# LED.net
KiCad netlist of a schematic drawn in EAGLE
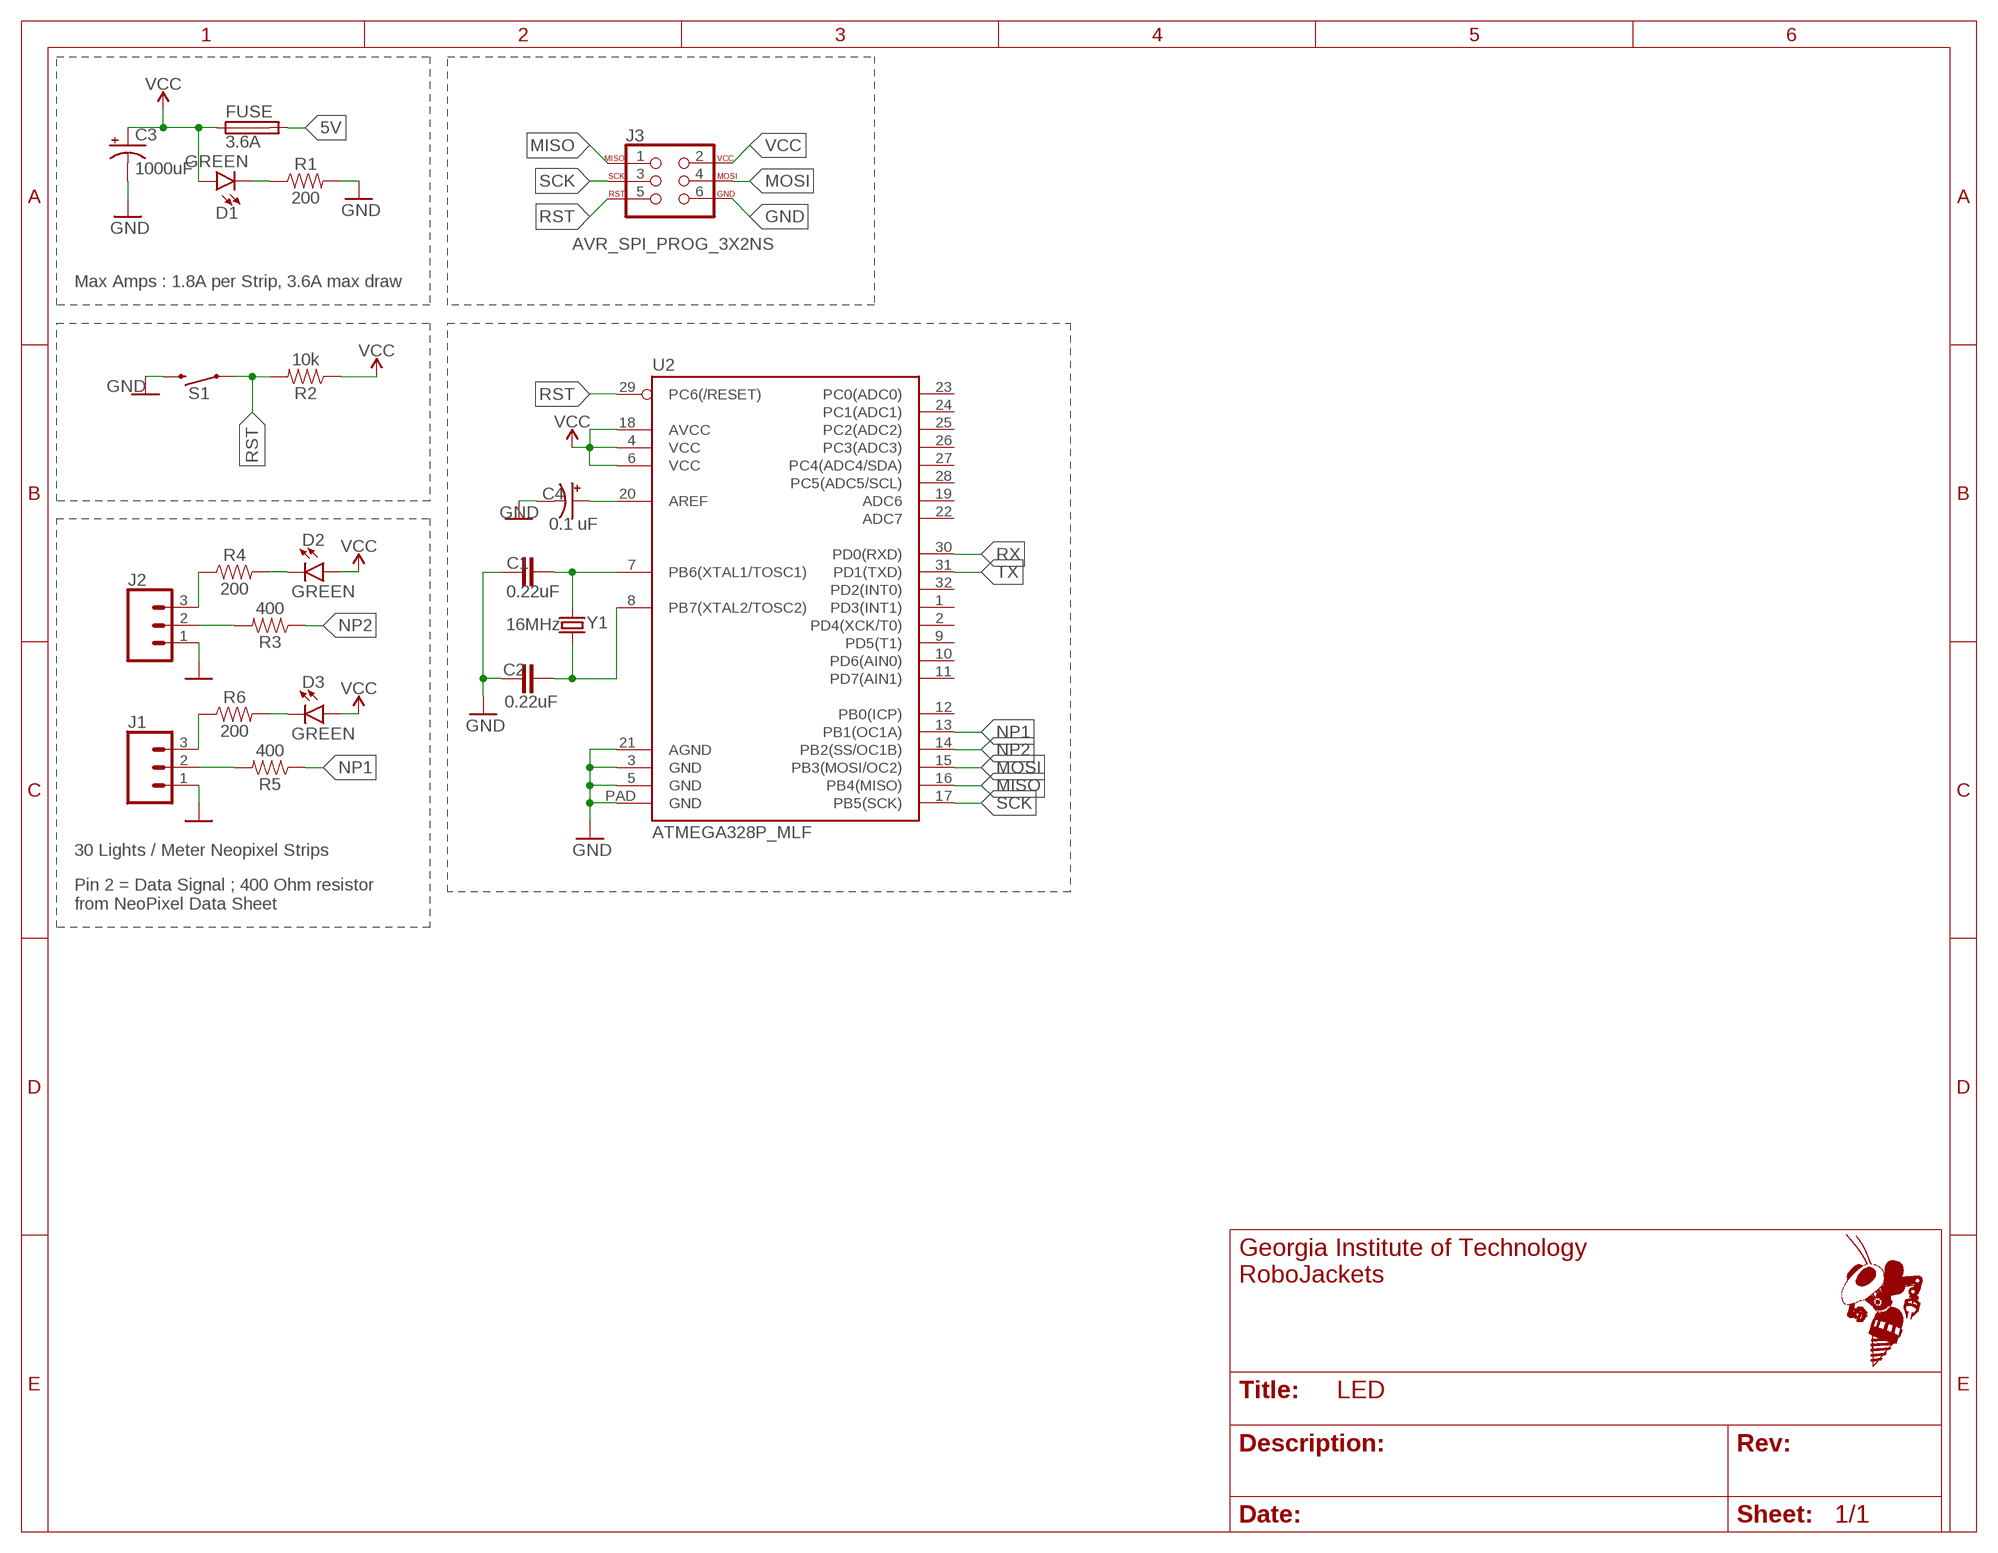
[diagram p0: schematic, sheet 1]

(export (version "E")
  (design (tool "Eeschema 10.0.6"))
  (components
    (comp (ref "C1")
      (value "0.22uF")
      (footprint "eagle-import:0603")
      (libsource (lib "eagle-import") (part "0.22UF-0603-25V-10%"))
    )
    (comp (ref "C2")
      (value "0.22uF")
      (footprint "eagle-import:0603")
      (libsource (lib "eagle-import") (part "0.22UF-0603-25V-10%"))
    )
    (comp (ref "C3")
      (value "1000uF")
      (footprint "eagle-import:CPOL-RADIAL-5MM-10MM")
      (libsource (lib "eagle-import") (part "1000UF-RADIAL-5MM-25V-20%"))
    )
    (comp (ref "C4")
      (value "0.1 uF")
      (footprint "eagle-import:CPOL-RADIAL-5MM-10MM")
      (libsource (lib "eagle-import") (part "1000UF-RADIAL-5MM-25V-20%"))
    )
    (comp (ref "D1")
      (value "GREEN")
      (footprint "eagle-import:LED-0603")
      (libsource (lib "eagle-import") (part "LED-GREEN0603"))
    )
    (comp (ref "D2")
      (value "GREEN")
      (footprint "eagle-import:LED-0603")
      (libsource (lib "eagle-import") (part "LED-GREEN0603"))
    )
    (comp (ref "D3")
      (value "GREEN")
      (footprint "eagle-import:LED-0603")
      (libsource (lib "eagle-import") (part "LED-GREEN0603"))
    )
    (comp (ref "FUSE")
      (value "3.6A")
      (footprint "eagle-import:FUSE_HOLDER")
      (libsource (lib "eagle-import") (part "FUSE_HOLDER"))
    )
    (comp (ref "J1")
      (value "CONN_03")
      (footprint "eagle-import:1X03")
      (fields (field (name "SPICEPREFIX") "J"))
      (libsource (lib "eagle-import") (part "CONN_03"))
    )
    (comp (ref "J2")
      (value "CONN_03")
      (footprint "eagle-import:1X03")
      (fields (field (name "SPICEPREFIX") "J"))
      (libsource (lib "eagle-import") (part "CONN_03"))
    )
    (comp (ref "J3")
      (value "AVR_SPI_PROG_3X2NS")
      (footprint "eagle-import:2X3-NS")
      (libsource (lib "eagle-import") (part "AVR_SPI_PROG_3X2NS"))
    )
    (comp (ref "R1")
      (value "200")
      (footprint "eagle-import:0603")
      (libsource (lib "eagle-import") (part "470OHM-0603-1/10W-1%"))
    )
    (comp (ref "R2")
      (value "10k")
      (footprint "eagle-import:0603")
      (libsource (lib "eagle-import") (part "470OHM-0603-1/10W-1%"))
    )
    (comp (ref "R3")
      (value "400")
      (footprint "eagle-import:0603")
      (libsource (lib "eagle-import") (part "470OHM-0603-1/10W-1%"))
    )
    (comp (ref "R4")
      (value "200")
      (footprint "eagle-import:0603")
      (libsource (lib "eagle-import") (part "470OHM-0603-1/10W-1%"))
    )
    (comp (ref "R5")
      (value "400")
      (footprint "eagle-import:0603")
      (libsource (lib "eagle-import") (part "470OHM-0603-1/10W-1%"))
    )
    (comp (ref "R6")
      (value "200")
      (footprint "eagle-import:0603")
      (libsource (lib "eagle-import") (part "470OHM-0603-1/10W-1%"))
    )
    (comp (ref "S1")
      (value "MOMENTARY-SWITCH-SPST-PTH-6.0MM-KIT")
      (footprint "eagle-import:TACTILE_SWITCH_PTH_6.0MM_KIT")
      (libsource (lib "eagle-import") (part "MOMENTARY-SWITCH-SPST-PTH-6.0MM-KIT"))
    )
    (comp (ref "U2")
      (value "ATMEGA328P_MLF")
      (footprint "eagle-import:MLF32-PAD")
      (libsource (lib "eagle-import") (part "ATMEGA328P_MLFMLF32"))
    )
    (comp (ref "Y1")
      (value "16MHz")
      (footprint "eagle-import:HC49US")
      (libsource (lib "eagle-import") (part "CRYSTAL-16MHZPTH-HC49US"))
    )
  )
  (nets
    (net (code "1") (name "5V") (class "Default")
      (node (ref "FUSE") (pin "P$3") (pinfunction "2_P$3") (pintype "passive"))
      (node (ref "FUSE") (pin "P$4") (pinfunction "2_P$4") (pintype "passive"))
    )
    (net (code "2") (name "GND") (class "Default")
      (node (ref "C1") (pin "2") (pinfunction "2_2") (pintype "passive"))
      (node (ref "C2") (pin "2") (pinfunction "2_2") (pintype "passive"))
      (node (ref "C3") (pin "-") (pinfunction "-_-") (pintype "passive"))
      (node (ref "C4") (pin "-") (pinfunction "-_-") (pintype "passive"))
      (node (ref "J1") (pin "1") (pinfunction "1_1") (pintype "passive"))
      (node (ref "J2") (pin "1") (pinfunction "1_1") (pintype "passive"))
      (node (ref "J3") (pin "6") (pinfunction "6_6") (pintype "passive"))
      (node (ref "R1") (pin "2") (pinfunction "2_2") (pintype "passive"))
      (node (ref "S1") (pin "3") (pinfunction "2_3") (pintype "passive"))
      (node (ref "U2") (pin "21") (pinfunction "AGND_21") (pintype "bidirectional"))
      (node (ref "U2") (pin "3") (pinfunction "GND_3") (pintype "bidirectional"))
      (node (ref "U2") (pin "5") (pinfunction "GND_5") (pintype "bidirectional"))
      (node (ref "U2") (pin "PAD") (pinfunction "GND_PAD") (pintype "bidirectional"))
    )
    (net (code "3") (name "MISO") (class "Default")
      (node (ref "J3") (pin "1") (pinfunction "1_1") (pintype "passive"))
      (node (ref "U2") (pin "16") (pinfunction "PB4(MISO)_16") (pintype "bidirectional"))
    )
    (net (code "4") (name "MOSI") (class "Default")
      (node (ref "J3") (pin "4") (pinfunction "4_4") (pintype "passive"))
      (node (ref "U2") (pin "15") (pinfunction "PB3(MOSI/OC2)_15") (pintype "bidirectional"))
    )
    (net (code "5") (name "NP1") (class "Default")
      (node (ref "R5") (pin "1") (pinfunction "1_1") (pintype "passive"))
      (node (ref "U2") (pin "13") (pinfunction "PB1(OC1A)_13") (pintype "bidirectional"))
    )
    (net (code "6") (name "NP2") (class "Default")
      (node (ref "R3") (pin "1") (pinfunction "1_1") (pintype "passive"))
      (node (ref "U2") (pin "14") (pinfunction "PB2(SS/OC1B)_14") (pintype "bidirectional"))
    )
    (net (code "7") (name "Net-(D1-PadC)") (class "Default")
      (node (ref "D1") (pin "C") (pinfunction "C_C") (pintype "passive"))
      (node (ref "R1") (pin "1") (pinfunction "1_1") (pintype "passive"))
    )
    (net (code "8") (name "Net-(D2-PadC)") (class "Default")
      (node (ref "D2") (pin "C") (pinfunction "C_C") (pintype "passive"))
      (node (ref "R4") (pin "2") (pinfunction "2_2") (pintype "passive"))
    )
    (net (code "9") (name "Net-(D3-PadC)") (class "Default")
      (node (ref "D3") (pin "C") (pinfunction "C_C") (pintype "passive"))
      (node (ref "R6") (pin "2") (pinfunction "2_2") (pintype "passive"))
    )
    (net (code "10") (name "Net-(J1-Pad2)") (class "Default")
      (node (ref "J1") (pin "2") (pinfunction "2_2") (pintype "passive"))
      (node (ref "R5") (pin "2") (pinfunction "2_2") (pintype "passive"))
    )
    (net (code "11") (name "Net-(J1-Pad3)") (class "Default")
      (node (ref "J1") (pin "3") (pinfunction "3_3") (pintype "passive"))
      (node (ref "R6") (pin "1") (pinfunction "1_1") (pintype "passive"))
    )
    (net (code "12") (name "Net-(J2-Pad2)") (class "Default")
      (node (ref "J2") (pin "2") (pinfunction "2_2") (pintype "passive"))
      (node (ref "R3") (pin "2") (pinfunction "2_2") (pintype "passive"))
    )
    (net (code "13") (name "Net-(J2-Pad3)") (class "Default")
      (node (ref "J2") (pin "3") (pinfunction "3_3") (pintype "passive"))
      (node (ref "R4") (pin "1") (pinfunction "1_1") (pintype "passive"))
    )
    (net (code "14") (name "Net-(U2-AREF)") (class "Default")
      (node (ref "C4") (pin "+") (pinfunction "+_+") (pintype "passive"))
      (node (ref "U2") (pin "20") (pinfunction "AREF_20") (pintype "bidirectional"))
    )
    (net (code "15") (name "Net-(U2-PB6(XTAL1{slash}TOSC1))") (class "Default")
      (node (ref "C1") (pin "1") (pinfunction "1_1") (pintype "passive"))
      (node (ref "U2") (pin "7") (pinfunction "PB6(XTAL1/TOSC1)_7") (pintype "bidirectional"))
      (node (ref "Y1") (pin "1") (pinfunction "1_1") (pintype "passive"))
    )
    (net (code "16") (name "Net-(U2-PB7(XTAL2{slash}TOSC2))") (class "Default")
      (node (ref "C2") (pin "1") (pinfunction "1_1") (pintype "passive"))
      (node (ref "U2") (pin "8") (pinfunction "PB7(XTAL2/TOSC2)_8") (pintype "bidirectional"))
      (node (ref "Y1") (pin "2") (pinfunction "2_2") (pintype "passive"))
    )
    (net (code "17") (name "RST") (class "Default")
      (node (ref "J3") (pin "5") (pinfunction "5_5") (pintype "passive"))
      (node (ref "R2") (pin "2") (pinfunction "2_2") (pintype "passive"))
      (node (ref "S1") (pin "1") (pinfunction "1_1") (pintype "passive"))
      (node (ref "U2") (pin "29") (pinfunction "PC6(/RESET)_29") (pintype "bidirectional"))
    )
    (net (code "18") (name "RX") (class "Default")
      (node (ref "U2") (pin "30") (pinfunction "PD0(RXD)_30") (pintype "bidirectional"))
    )
    (net (code "19") (name "SCK") (class "Default")
      (node (ref "J3") (pin "3") (pinfunction "3_3") (pintype "passive"))
      (node (ref "U2") (pin "17") (pinfunction "PB5(SCK)_17") (pintype "bidirectional"))
    )
    (net (code "20") (name "TX") (class "Default")
      (node (ref "U2") (pin "31") (pinfunction "PD1(TXD)_31") (pintype "bidirectional"))
    )
    (net (code "21") (name "VCC") (class "Default")
      (node (ref "C3") (pin "+") (pinfunction "+_+") (pintype "passive"))
      (node (ref "D1") (pin "A") (pinfunction "A_A") (pintype "passive"))
      (node (ref "D2") (pin "A") (pinfunction "A_A") (pintype "passive"))
      (node (ref "D3") (pin "A") (pinfunction "A_A") (pintype "passive"))
      (node (ref "FUSE") (pin "P$1") (pinfunction "1_P$1") (pintype "passive"))
      (node (ref "FUSE") (pin "P$2") (pinfunction "1_P$2") (pintype "passive"))
      (node (ref "J3") (pin "2") (pinfunction "2_2") (pintype "passive"))
      (node (ref "R2") (pin "1") (pinfunction "1_1") (pintype "passive"))
      (node (ref "U2") (pin "18") (pinfunction "AVCC_18") (pintype "bidirectional"))
      (node (ref "U2") (pin "4") (pinfunction "VCC_4") (pintype "bidirectional"))
      (node (ref "U2") (pin "6") (pinfunction "VCC_6") (pintype "bidirectional"))
    )
    (net (code "22") (name "unconnected-(U2-ADC6-Pad19)") (class "Default")
      (node (ref "U2") (pin "19") (pinfunction "ADC6_19") (pintype "bidirectional"))
    )
    (net (code "23") (name "unconnected-(U2-ADC7-Pad22)") (class "Default")
      (node (ref "U2") (pin "22") (pinfunction "ADC7_22") (pintype "bidirectional"))
    )
    (net (code "24") (name "unconnected-(U2-PB0(ICP)-Pad12)") (class "Default")
      (node (ref "U2") (pin "12") (pinfunction "PB0(ICP)_12") (pintype "bidirectional"))
    )
    (net (code "25") (name "unconnected-(U2-PC0(ADC0)-Pad23)") (class "Default")
      (node (ref "U2") (pin "23") (pinfunction "PC0(ADC0)_23") (pintype "bidirectional"))
    )
    (net (code "26") (name "unconnected-(U2-PC1(ADC1)-Pad24)") (class "Default")
      (node (ref "U2") (pin "24") (pinfunction "PC1(ADC1)_24") (pintype "bidirectional"))
    )
    (net (code "27") (name "unconnected-(U2-PC2(ADC2)-Pad25)") (class "Default")
      (node (ref "U2") (pin "25") (pinfunction "PC2(ADC2)_25") (pintype "bidirectional"))
    )
    (net (code "28") (name "unconnected-(U2-PC3(ADC3)-Pad26)") (class "Default")
      (node (ref "U2") (pin "26") (pinfunction "PC3(ADC3)_26") (pintype "bidirectional"))
    )
    (net (code "29") (name "unconnected-(U2-PC4(ADC4{slash}SDA)-Pad27)") (class "Default")
      (node (ref "U2") (pin "27") (pinfunction "PC4(ADC4/SDA)_27") (pintype "bidirectional"))
    )
    (net (code "30") (name "unconnected-(U2-PC5(ADC5{slash}SCL)-Pad28)") (class "Default")
      (node (ref "U2") (pin "28") (pinfunction "PC5(ADC5/SCL)_28") (pintype "bidirectional"))
    )
    (net (code "31") (name "unconnected-(U2-PD2(INT0)-Pad32)") (class "Default")
      (node (ref "U2") (pin "32") (pinfunction "PD2(INT0)_32") (pintype "bidirectional"))
    )
    (net (code "32") (name "unconnected-(U2-PD3(INT1)-Pad1)") (class "Default")
      (node (ref "U2") (pin "1") (pinfunction "PD3(INT1)_1") (pintype "bidirectional"))
    )
    (net (code "33") (name "unconnected-(U2-PD4(XCK{slash}T0)-Pad2)") (class "Default")
      (node (ref "U2") (pin "2") (pinfunction "PD4(XCK/T0)_2") (pintype "bidirectional"))
    )
    (net (code "34") (name "unconnected-(U2-PD5(T1)-Pad9)") (class "Default")
      (node (ref "U2") (pin "9") (pinfunction "PD5(T1)_9") (pintype "bidirectional"))
    )
    (net (code "35") (name "unconnected-(U2-PD6(AIN0)-Pad10)") (class "Default")
      (node (ref "U2") (pin "10") (pinfunction "PD6(AIN0)_10") (pintype "bidirectional"))
    )
    (net (code "36") (name "unconnected-(U2-PD7(AIN1)-Pad11)") (class "Default")
      (node (ref "U2") (pin "11") (pinfunction "PD7(AIN1)_11") (pintype "bidirectional"))
    )
  )
)
